# LCD-Touch-Exp.net
KiCad netlist of a schematic drawn in EAGLE
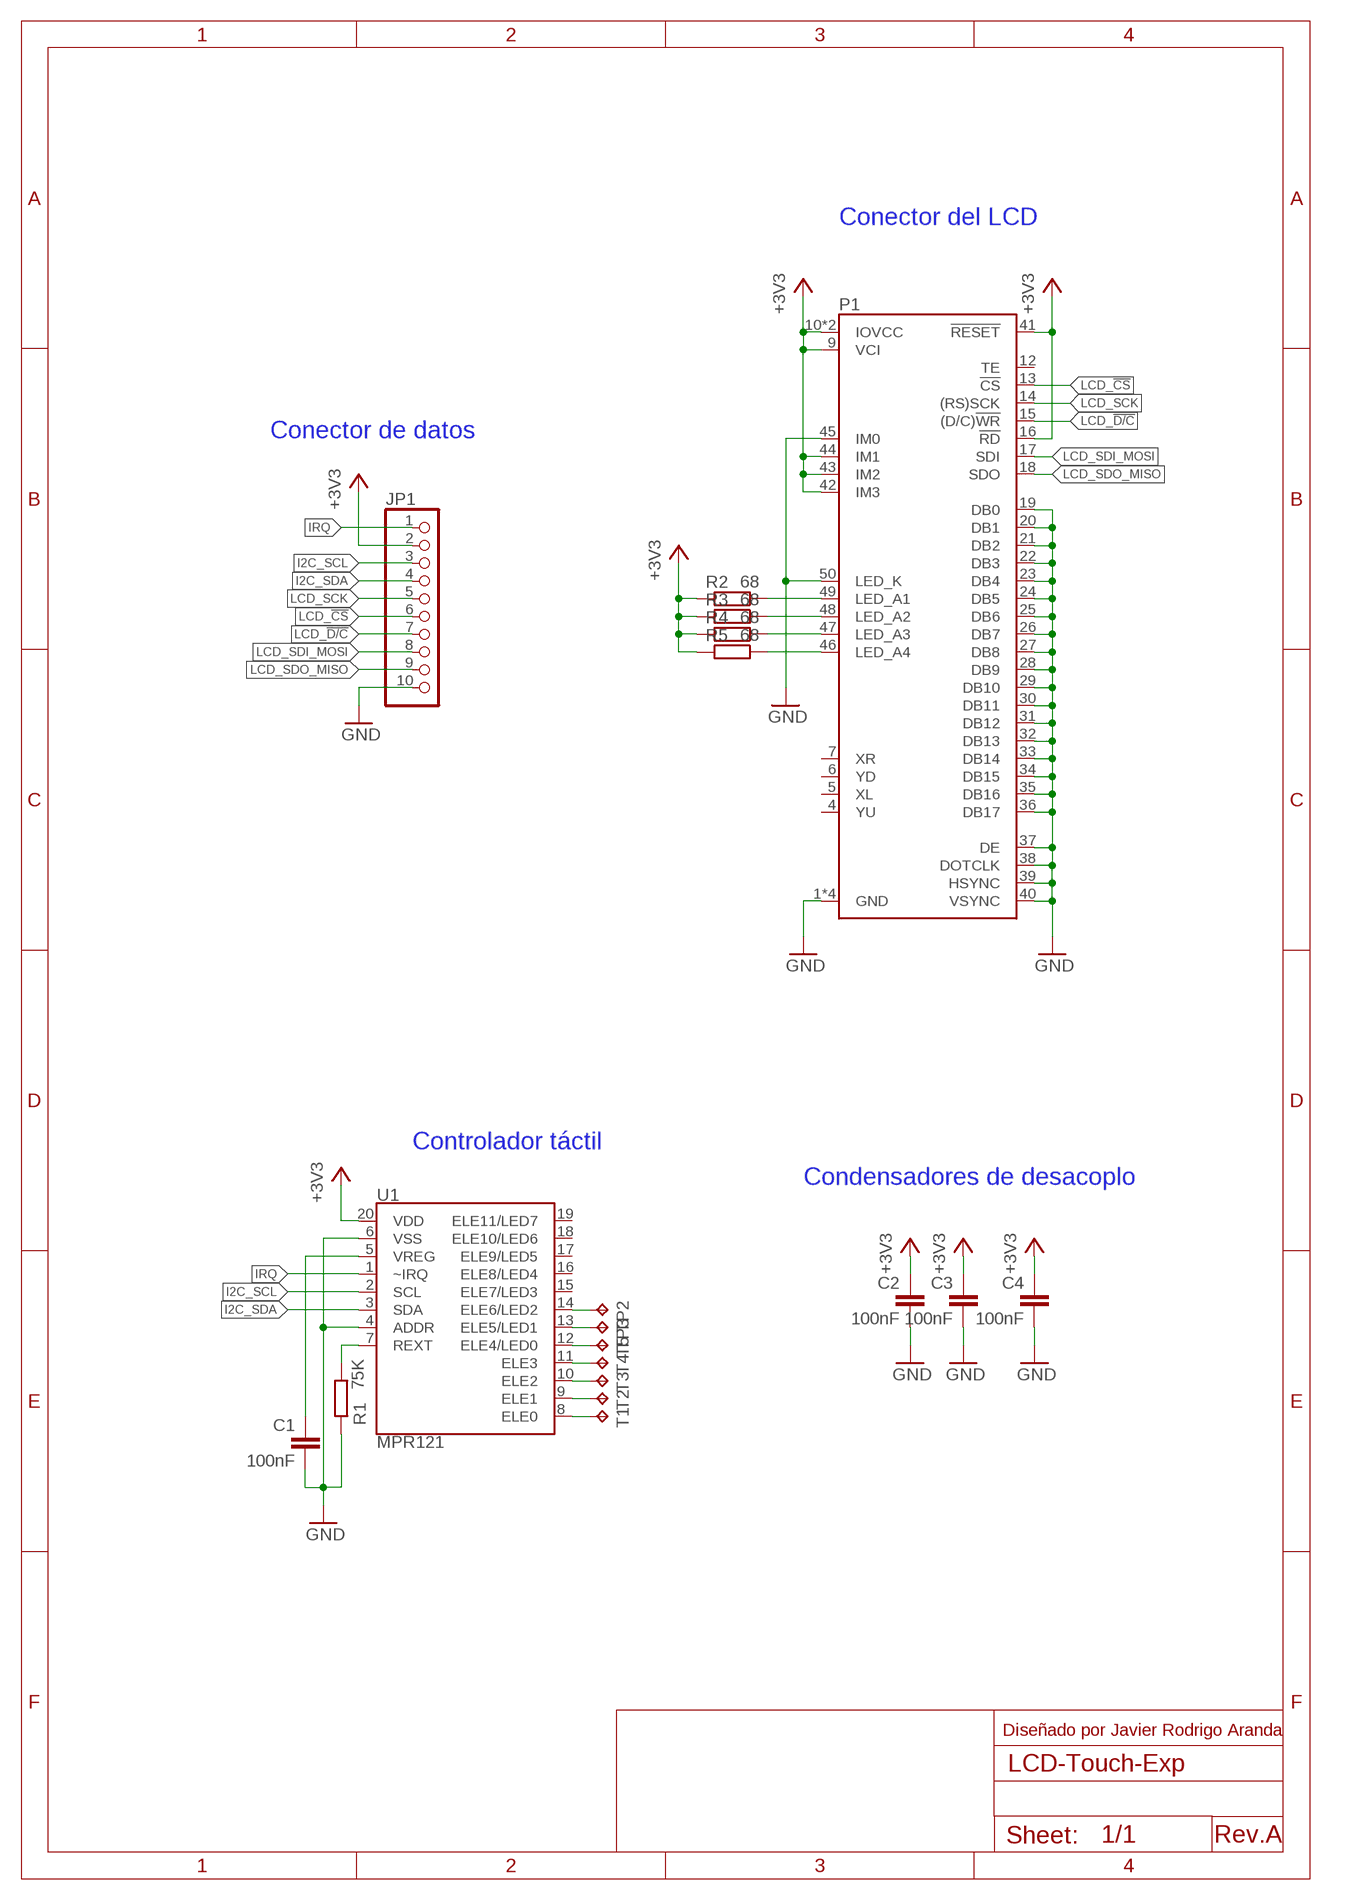
[diagram p0: schematic, sheet 1]

(export (version "E")
  (design (tool "Eeschema 10.0.6"))
  (components
    (comp (ref "C1")
      (value "100nF")
      (footprint "eagle-import:C0805")
      (libsource (lib "eagle-import") (part "C-EUC0805"))
    )
    (comp (ref "C2")
      (value "100nF")
      (footprint "eagle-import:C0805")
      (libsource (lib "eagle-import") (part "C-EUC0805"))
    )
    (comp (ref "C3")
      (value "100nF")
      (footprint "eagle-import:C0805")
      (libsource (lib "eagle-import") (part "C-EUC0805"))
    )
    (comp (ref "C4")
      (value "100nF")
      (footprint "eagle-import:C0805")
      (libsource (lib "eagle-import") (part "C-EUC0805"))
    )
    (comp (ref "JP1")
      (value "HEADER-1X10SMT")
      (footprint "eagle-import:1X10_SMT")
      (libsource (lib "eagle-import") (part "HEADER-1X10SMT"))
    )
    (comp (ref "P1")
      (value "LCD_ILI9341180º")
      (footprint "eagle-import:FPC-50P-0.5MM")
      (libsource (lib "eagle-import") (part "LCD_ILI9341180º"))
    )
    (comp (ref "R1")
      (value "75K")
      (footprint "eagle-import:R0805")
      (libsource (lib "eagle-import") (part "R-EU_R0805"))
    )
    (comp (ref "R2")
      (value "68")
      (footprint "eagle-import:R0603")
      (libsource (lib "eagle-import") (part "R-EU_R0603"))
    )
    (comp (ref "R3")
      (value "68")
      (footprint "eagle-import:R0603")
      (libsource (lib "eagle-import") (part "R-EU_R0603"))
    )
    (comp (ref "R4")
      (value "68")
      (footprint "eagle-import:R0603")
      (libsource (lib "eagle-import") (part "R-EU_R0603"))
    )
    (comp (ref "R5")
      (value "68")
      (footprint "eagle-import:R0603")
      (libsource (lib "eagle-import") (part "R-EU_R0603"))
    )
    (comp (ref "T1")
      (value "TPB1,27")
      (footprint "eagle-import:B1,27")
      (libsource (lib "eagle-import") (part "TPB1,27"))
    )
    (comp (ref "T2")
      (value "TPB1,27")
      (footprint "eagle-import:B1,27")
      (libsource (lib "eagle-import") (part "TPB1,27"))
    )
    (comp (ref "T3")
      (value "TPB1,27")
      (footprint "eagle-import:B1,27")
      (libsource (lib "eagle-import") (part "TPB1,27"))
    )
    (comp (ref "T4")
      (value "TPB1,27")
      (footprint "eagle-import:B1,27")
      (libsource (lib "eagle-import") (part "TPB1,27"))
    )
    (comp (ref "T5")
      (value "TPB1,27")
      (footprint "eagle-import:B1,27")
      (libsource (lib "eagle-import") (part "TPB1,27"))
    )
    (comp (ref "TP2")
      (value "TPB1,27")
      (footprint "eagle-import:B1,27")
      (libsource (lib "eagle-import") (part "TPB1,27"))
    )
    (comp (ref "TP3")
      (value "TPB1,27")
      (footprint "eagle-import:B1,27")
      (libsource (lib "eagle-import") (part "TPB1,27"))
    )
    (comp (ref "U1")
      (value "MPR121")
      (footprint "eagle-import:QFN-20")
      (libsource (lib "eagle-import") (part "MPR121"))
    )
  )
  (nets
    (net (code "1") (name "+3V3") (class "Default")
      (node (ref "C2") (pin "1") (pinfunction "1_1") (pintype "passive"))
      (node (ref "C3") (pin "1") (pinfunction "1_1") (pintype "passive"))
      (node (ref "C4") (pin "1") (pinfunction "1_1") (pintype "passive"))
      (node (ref "JP1") (pin "2") (pinfunction "2_2") (pintype "passive"))
      (node (ref "P1") (pin "10") (pinfunction "IOVCC_10") (pintype "bidirectional"))
      (node (ref "P1") (pin "11") (pinfunction "IOVCC_11") (pintype "bidirectional"))
      (node (ref "P1") (pin "16") (pinfunction "~{RD}_16") (pintype "bidirectional"))
      (node (ref "P1") (pin "41") (pinfunction "~{RESET}_41") (pintype "bidirectional"))
      (node (ref "P1") (pin "42") (pinfunction "IM3_42") (pintype "bidirectional"))
      (node (ref "P1") (pin "43") (pinfunction "IM2_43") (pintype "bidirectional"))
      (node (ref "P1") (pin "44") (pinfunction "IM1_44") (pintype "bidirectional"))
      (node (ref "P1") (pin "9") (pinfunction "VCI_9") (pintype "bidirectional"))
      (node (ref "R2") (pin "2") (pinfunction "2_2") (pintype "passive"))
      (node (ref "R3") (pin "2") (pinfunction "2_2") (pintype "passive"))
      (node (ref "R4") (pin "2") (pinfunction "2_2") (pintype "passive"))
      (node (ref "R5") (pin "2") (pinfunction "2_2") (pintype "passive"))
      (node (ref "U1") (pin "20") (pinfunction "VDD_20") (pintype "bidirectional"))
    )
    (net (code "2") (name "/LCD_~{CS}") (class "Default")
      (node (ref "JP1") (pin "6") (pinfunction "6_6") (pintype "passive"))
      (node (ref "P1") (pin "13") (pinfunction "~{CS}_13") (pintype "bidirectional"))
    )
    (net (code "3") (name "/LCD_~{D{slash}C}") (class "Default")
      (node (ref "JP1") (pin "7") (pinfunction "7_7") (pintype "passive"))
      (node (ref "P1") (pin "15") (pinfunction "(D/C)~{WR}_15") (pintype "bidirectional"))
    )
    (net (code "4") (name "GND") (class "Default")
      (node (ref "C1") (pin "2") (pinfunction "2_2") (pintype "passive"))
      (node (ref "C2") (pin "2") (pinfunction "2_2") (pintype "passive"))
      (node (ref "C3") (pin "2") (pinfunction "2_2") (pintype "passive"))
      (node (ref "C4") (pin "2") (pinfunction "2_2") (pintype "passive"))
      (node (ref "JP1") (pin "10") (pinfunction "10_10") (pintype "passive"))
      (node (ref "P1") (pin "1") (pinfunction "GND_1") (pintype "bidirectional"))
      (node (ref "P1") (pin "19") (pinfunction "DB0_19") (pintype "bidirectional"))
      (node (ref "P1") (pin "2") (pinfunction "GND_2") (pintype "bidirectional"))
      (node (ref "P1") (pin "20") (pinfunction "DB1_20") (pintype "bidirectional"))
      (node (ref "P1") (pin "21") (pinfunction "DB2_21") (pintype "bidirectional"))
      (node (ref "P1") (pin "22") (pinfunction "DB3_22") (pintype "bidirectional"))
      (node (ref "P1") (pin "23") (pinfunction "DB4_23") (pintype "bidirectional"))
      (node (ref "P1") (pin "24") (pinfunction "DB5_24") (pintype "bidirectional"))
      (node (ref "P1") (pin "25") (pinfunction "DB6_25") (pintype "bidirectional"))
      (node (ref "P1") (pin "26") (pinfunction "DB7_26") (pintype "bidirectional"))
      (node (ref "P1") (pin "27") (pinfunction "DB8_27") (pintype "bidirectional"))
      (node (ref "P1") (pin "28") (pinfunction "DB9_28") (pintype "bidirectional"))
      (node (ref "P1") (pin "29") (pinfunction "DB10_29") (pintype "bidirectional"))
      (node (ref "P1") (pin "3") (pinfunction "GND_3") (pintype "bidirectional"))
      (node (ref "P1") (pin "30") (pinfunction "DB11_30") (pintype "bidirectional"))
      (node (ref "P1") (pin "31") (pinfunction "DB12_31") (pintype "bidirectional"))
      (node (ref "P1") (pin "32") (pinfunction "DB13_32") (pintype "bidirectional"))
      (node (ref "P1") (pin "33") (pinfunction "DB14_33") (pintype "bidirectional"))
      (node (ref "P1") (pin "34") (pinfunction "DB15_34") (pintype "bidirectional"))
      (node (ref "P1") (pin "35") (pinfunction "DB16_35") (pintype "bidirectional"))
      (node (ref "P1") (pin "36") (pinfunction "DB17_36") (pintype "bidirectional"))
      (node (ref "P1") (pin "37") (pinfunction "DE_37") (pintype "bidirectional"))
      (node (ref "P1") (pin "38") (pinfunction "DOTCLK_38") (pintype "bidirectional"))
      (node (ref "P1") (pin "39") (pinfunction "HSYNC_39") (pintype "bidirectional"))
      (node (ref "P1") (pin "40") (pinfunction "VSYNC_40") (pintype "bidirectional"))
      (node (ref "P1") (pin "45") (pinfunction "IM0_45") (pintype "bidirectional"))
      (node (ref "P1") (pin "50") (pinfunction "LED_K_50") (pintype "bidirectional"))
      (node (ref "P1") (pin "8") (pinfunction "GND_8") (pintype "bidirectional"))
      (node (ref "R1") (pin "1") (pinfunction "1_1") (pintype "passive"))
      (node (ref "U1") (pin "4") (pinfunction "ADDR_4") (pintype "bidirectional"))
      (node (ref "U1") (pin "6") (pinfunction "VSS_6") (pintype "bidirectional"))
    )
    (net (code "5") (name "I2C_SCL") (class "Default")
      (node (ref "JP1") (pin "3") (pinfunction "3_3") (pintype "passive"))
      (node (ref "U1") (pin "2") (pinfunction "SCL_2") (pintype "bidirectional"))
    )
    (net (code "6") (name "I2C_SDA") (class "Default")
      (node (ref "JP1") (pin "4") (pinfunction "4_4") (pintype "passive"))
      (node (ref "U1") (pin "3") (pinfunction "SDA_3") (pintype "bidirectional"))
    )
    (net (code "7") (name "IRQ") (class "Default")
      (node (ref "JP1") (pin "1") (pinfunction "1_1") (pintype "passive"))
      (node (ref "U1") (pin "1") (pinfunction "~{IRQ}_1") (pintype "bidirectional"))
    )
    (net (code "8") (name "LCD_SCK") (class "Default")
      (node (ref "JP1") (pin "5") (pinfunction "5_5") (pintype "passive"))
      (node (ref "P1") (pin "14") (pinfunction "(RS)SCK_14") (pintype "bidirectional"))
    )
    (net (code "9") (name "LCD_SDI_MOSI") (class "Default")
      (node (ref "JP1") (pin "8") (pinfunction "8_8") (pintype "passive"))
      (node (ref "P1") (pin "17") (pinfunction "SDI_17") (pintype "bidirectional"))
    )
    (net (code "10") (name "LCD_SDO_MISO") (class "Default")
      (node (ref "JP1") (pin "9") (pinfunction "9_9") (pintype "passive"))
      (node (ref "P1") (pin "18") (pinfunction "SDO_18") (pintype "bidirectional"))
    )
    (net (code "11") (name "Net-(P1-LED_A1)") (class "Default")
      (node (ref "P1") (pin "49") (pinfunction "LED_A1_49") (pintype "bidirectional"))
      (node (ref "R2") (pin "1") (pinfunction "1_1") (pintype "passive"))
    )
    (net (code "12") (name "Net-(P1-LED_A2)") (class "Default")
      (node (ref "P1") (pin "48") (pinfunction "LED_A2_48") (pintype "bidirectional"))
      (node (ref "R3") (pin "1") (pinfunction "1_1") (pintype "passive"))
    )
    (net (code "13") (name "Net-(P1-LED_A3)") (class "Default")
      (node (ref "P1") (pin "47") (pinfunction "LED_A3_47") (pintype "bidirectional"))
      (node (ref "R4") (pin "1") (pinfunction "1_1") (pintype "passive"))
    )
    (net (code "14") (name "Net-(P1-LED_A4)") (class "Default")
      (node (ref "P1") (pin "46") (pinfunction "LED_A4_46") (pintype "bidirectional"))
      (node (ref "R5") (pin "1") (pinfunction "1_1") (pintype "passive"))
    )
    (net (code "15") (name "Net-(U1-ELE0)") (class "Default")
      (node (ref "T1") (pin "TP") (pinfunction "TP_TP") (pintype "input"))
      (node (ref "U1") (pin "8") (pinfunction "ELE0_8") (pintype "bidirectional"))
    )
    (net (code "16") (name "Net-(U1-ELE1)") (class "Default")
      (node (ref "T2") (pin "TP") (pinfunction "TP_TP") (pintype "input"))
      (node (ref "U1") (pin "9") (pinfunction "ELE1_9") (pintype "bidirectional"))
    )
    (net (code "17") (name "Net-(U1-ELE2)") (class "Default")
      (node (ref "T3") (pin "TP") (pinfunction "TP_TP") (pintype "input"))
      (node (ref "U1") (pin "10") (pinfunction "ELE2_10") (pintype "bidirectional"))
    )
    (net (code "18") (name "Net-(U1-ELE3)") (class "Default")
      (node (ref "T4") (pin "TP") (pinfunction "TP_TP") (pintype "input"))
      (node (ref "U1") (pin "11") (pinfunction "ELE3_11") (pintype "bidirectional"))
    )
    (net (code "19") (name "Net-(U1-ELE4{slash}LED0)") (class "Default")
      (node (ref "T5") (pin "TP") (pinfunction "TP_TP") (pintype "input"))
      (node (ref "U1") (pin "12") (pinfunction "ELE4/LED0_12") (pintype "bidirectional"))
    )
    (net (code "20") (name "Net-(U1-ELE5{slash}LED1)") (class "Default")
      (node (ref "TP3") (pin "TP") (pinfunction "TP_TP") (pintype "input"))
      (node (ref "U1") (pin "13") (pinfunction "ELE5/LED1_13") (pintype "bidirectional"))
    )
    (net (code "21") (name "Net-(U1-ELE6{slash}LED2)") (class "Default")
      (node (ref "TP2") (pin "TP") (pinfunction "TP_TP") (pintype "input"))
      (node (ref "U1") (pin "14") (pinfunction "ELE6/LED2_14") (pintype "bidirectional"))
    )
    (net (code "22") (name "Net-(U1-REXT)") (class "Default")
      (node (ref "R1") (pin "2") (pinfunction "2_2") (pintype "passive"))
      (node (ref "U1") (pin "7") (pinfunction "REXT_7") (pintype "bidirectional"))
    )
    (net (code "23") (name "Net-(U1-VREG)") (class "Default")
      (node (ref "C1") (pin "1") (pinfunction "1_1") (pintype "passive"))
      (node (ref "U1") (pin "5") (pinfunction "VREG_5") (pintype "bidirectional"))
    )
    (net (code "24") (name "unconnected-(P1-TE-Pad12)") (class "Default")
      (node (ref "P1") (pin "12") (pinfunction "TE_12") (pintype "bidirectional"))
    )
    (net (code "25") (name "unconnected-(P1-XL-Pad5)") (class "Default")
      (node (ref "P1") (pin "5") (pinfunction "XL_5") (pintype "bidirectional"))
    )
    (net (code "26") (name "unconnected-(P1-XR-Pad7)") (class "Default")
      (node (ref "P1") (pin "7") (pinfunction "XR_7") (pintype "bidirectional"))
    )
    (net (code "27") (name "unconnected-(P1-YD-Pad6)") (class "Default")
      (node (ref "P1") (pin "6") (pinfunction "YD_6") (pintype "bidirectional"))
    )
    (net (code "28") (name "unconnected-(P1-YU-Pad4)") (class "Default")
      (node (ref "P1") (pin "4") (pinfunction "YU_4") (pintype "bidirectional"))
    )
    (net (code "29") (name "unconnected-(U1-ELE7{slash}LED3-Pad15)") (class "Default")
      (node (ref "U1") (pin "15") (pinfunction "ELE7/LED3_15") (pintype "bidirectional"))
    )
    (net (code "30") (name "unconnected-(U1-ELE8{slash}LED4-Pad16)") (class "Default")
      (node (ref "U1") (pin "16") (pinfunction "ELE8/LED4_16") (pintype "bidirectional"))
    )
    (net (code "31") (name "unconnected-(U1-ELE9{slash}LED5-Pad17)") (class "Default")
      (node (ref "U1") (pin "17") (pinfunction "ELE9/LED5_17") (pintype "bidirectional"))
    )
    (net (code "32") (name "unconnected-(U1-ELE10{slash}LED6-Pad18)") (class "Default")
      (node (ref "U1") (pin "18") (pinfunction "ELE10/LED6_18") (pintype "bidirectional"))
    )
    (net (code "33") (name "unconnected-(U1-ELE11{slash}LED7-Pad19)") (class "Default")
      (node (ref "U1") (pin "19") (pinfunction "ELE11/LED7_19") (pintype "bidirectional"))
    )
  )
)
